# MCU.net
KiCad netlist of a schematic drawn in Altium Designer
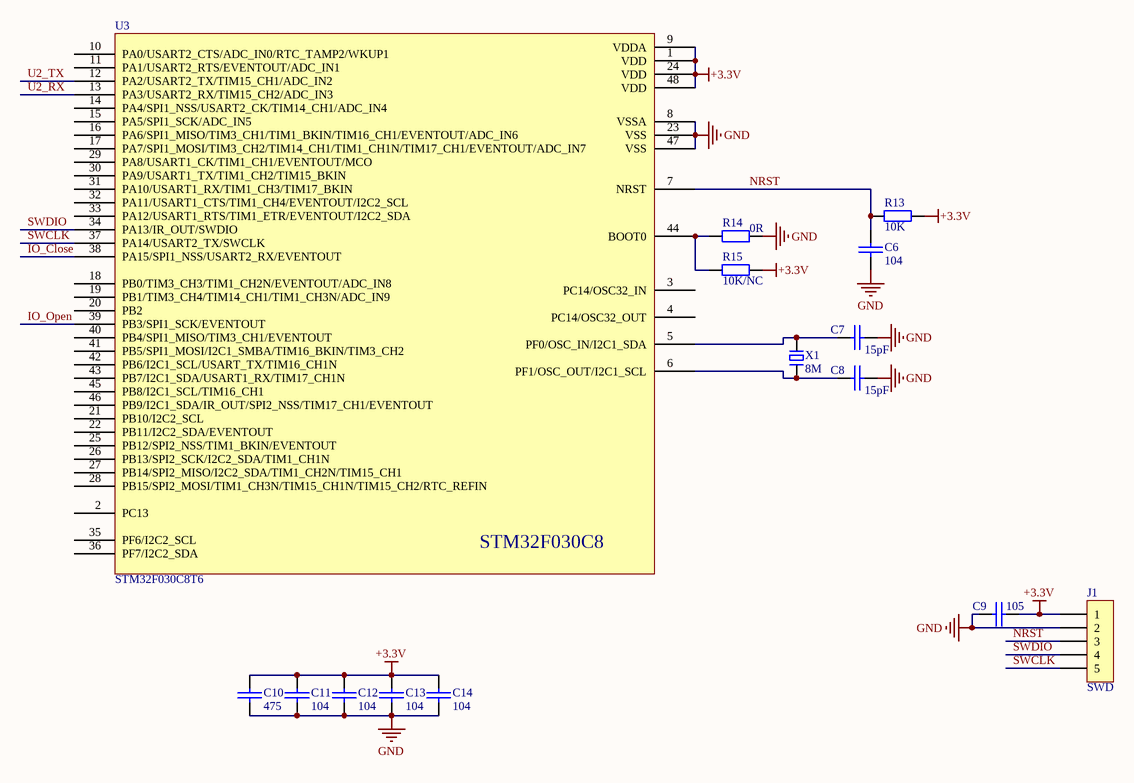
[diagram p0: MCU.SchDoc]

(export (version "E")
  (design (tool "Eeschema 10.0.6"))
  (components
    (comp (ref "C6")
      (value "104")
      (footprint "C0805")
      (description "贴片电容or无极性电容")
      (libsource (lib "LRC") (part "Cap"))
    )
    (comp (ref "C7")
      (value "15pF")
      (footprint "C0805")
      (description "贴片电容or无极性电容")
      (libsource (lib "LRC") (part "Cap"))
    )
    (comp (ref "C8")
      (value "15pF")
      (footprint "C0805")
      (description "贴片电容or无极性电容")
      (libsource (lib "LRC") (part "Cap"))
    )
    (comp (ref "C9")
      (value "105")
      (footprint "C0805")
      (description "贴片电容or无极性电容")
      (libsource (lib "LRC") (part "Cap"))
    )
    (comp (ref "C10")
      (value "475")
      (footprint "C0805")
      (description "贴片电容or无极性电容")
      (libsource (lib "LRC") (part "Cap"))
    )
    (comp (ref "C11")
      (value "104")
      (footprint "C0805")
      (description "贴片电容or无极性电容")
      (libsource (lib "LRC") (part "Cap"))
    )
    (comp (ref "C12")
      (value "104")
      (footprint "C0805")
      (description "贴片电容or无极性电容")
      (libsource (lib "LRC") (part "Cap"))
    )
    (comp (ref "C13")
      (value "104")
      (footprint "C0805")
      (description "贴片电容or无极性电容")
      (libsource (lib "LRC") (part "Cap"))
    )
    (comp (ref "C14")
      (value "104")
      (footprint "C0805")
      (description "贴片电容or无极性电容")
      (libsource (lib "LRC") (part "Cap"))
    )
    (comp (ref "J1")
      (value "SWD")
      (footprint "Fe-HDR1X5/2.54-S")
      (description "2.54MM排母  1x5")
      (libsource (lib "插接件") (part "Female HDR1X5"))
    )
    (comp (ref "R13")
      (value "10K")
      (footprint "R0805")
      (description "电阻")
      (libsource (lib "LRC") (part "Res"))
    )
    (comp (ref "R14")
      (value "0R")
      (footprint "R0805")
      (description "电阻")
      (libsource (lib "LRC") (part "Res"))
    )
    (comp (ref "R15")
      (value "10K/NC")
      (footprint "R0805")
      (description "电阻")
      (libsource (lib "LRC") (part "Res"))
    )
    (comp (ref "U3")
      (value "STM32F030C8T6")
      (footprint "LQFP48 7X7")
      (libsource (lib "IC") (part "STM32f030C8T6"))
    )
    (comp (ref "X1")
      (value "8M")
      (footprint "OSC 5032-2P")
      (description "2脚无源脚晶振")
      (libsource (lib "晶振") (part "XTAL-2P"))
    )
  )
  (nets
    (net (code "1") (name "+3.3V") (class "Default")
      (node (ref "C10") (pin "1") (pinfunction "1_1") (pintype "passive"))
      (node (ref "C11") (pin "1") (pinfunction "1_1") (pintype "passive"))
      (node (ref "C12") (pin "1") (pinfunction "1_1") (pintype "passive"))
      (node (ref "C13") (pin "1") (pinfunction "1_1") (pintype "passive"))
      (node (ref "C14") (pin "1") (pinfunction "1_1") (pintype "passive"))
      (node (ref "C9") (pin "1") (pinfunction "1_1") (pintype "passive"))
      (node (ref "J1") (pin "1") (pinfunction "1_1") (pintype "passive"))
      (node (ref "R13") (pin "2") (pinfunction "2_2") (pintype "passive"))
      (node (ref "R15") (pin "2") (pinfunction "2_2") (pintype "passive"))
      (node (ref "U3") (pin "1") (pinfunction "VDD_1") (pintype "passive"))
      (node (ref "U3") (pin "24") (pinfunction "VDD_24") (pintype "passive"))
      (node (ref "U3") (pin "48") (pinfunction "VDD_48") (pintype "passive"))
      (node (ref "U3") (pin "9") (pinfunction "VDDA_9") (pintype "passive"))
    )
    (net (code "2") (name "/IO_Close") (class "Default")
      (node (ref "U3") (pin "38") (pinfunction "PA15/SPI1_NSS/USART2_RX/EVENTOUT_38") (pintype "passive"))
    )
    (net (code "3") (name "/IO_Open") (class "Default")
      (node (ref "U3") (pin "39") (pinfunction "PB3/SPI1_SCK/EVENTOUT_39") (pintype "passive"))
    )
    (net (code "4") (name "/NRST") (class "Default")
      (node (ref "C6") (pin "1") (pinfunction "1_1") (pintype "passive"))
      (node (ref "J1") (pin "3") (pinfunction "3_3") (pintype "passive"))
      (node (ref "R13") (pin "1") (pinfunction "1_1") (pintype "passive"))
      (node (ref "U3") (pin "7") (pinfunction "NRST_7") (pintype "passive"))
    )
    (net (code "5") (name "/SWCLK") (class "Default")
      (node (ref "J1") (pin "5") (pinfunction "5_5") (pintype "passive"))
      (node (ref "U3") (pin "37") (pinfunction "PA14/USART2_TX/SWCLK_37") (pintype "passive"))
    )
    (net (code "6") (name "/SWDIO") (class "Default")
      (node (ref "J1") (pin "4") (pinfunction "4_4") (pintype "passive"))
      (node (ref "U3") (pin "34") (pinfunction "PA13/IR_OUT/SWDIO_34") (pintype "passive"))
    )
    (net (code "7") (name "/U2_RX") (class "Default")
      (node (ref "U3") (pin "13") (pinfunction "PA3/USART2_RX/TIM15_CH2/ADC_IN3_13") (pintype "passive"))
    )
    (net (code "8") (name "/U2_TX") (class "Default")
      (node (ref "U3") (pin "12") (pinfunction "PA2/USART2_TX/TIM15_CH1/ADC_IN2_12") (pintype "passive"))
    )
    (net (code "9") (name "GND") (class "Default")
      (node (ref "C10") (pin "2") (pinfunction "2_2") (pintype "passive"))
      (node (ref "C11") (pin "2") (pinfunction "2_2") (pintype "passive"))
      (node (ref "C12") (pin "2") (pinfunction "2_2") (pintype "passive"))
      (node (ref "C13") (pin "2") (pinfunction "2_2") (pintype "passive"))
      (node (ref "C14") (pin "2") (pinfunction "2_2") (pintype "passive"))
      (node (ref "C6") (pin "2") (pinfunction "2_2") (pintype "passive"))
      (node (ref "C7") (pin "1") (pinfunction "1_1") (pintype "passive"))
      (node (ref "C8") (pin "1") (pinfunction "1_1") (pintype "passive"))
      (node (ref "C9") (pin "2") (pinfunction "2_2") (pintype "passive"))
      (node (ref "J1") (pin "2") (pinfunction "2_2") (pintype "passive"))
      (node (ref "R14") (pin "2") (pinfunction "2_2") (pintype "passive"))
      (node (ref "U3") (pin "23") (pinfunction "VSS_23") (pintype "passive"))
      (node (ref "U3") (pin "47") (pinfunction "VSS_47") (pintype "passive"))
      (node (ref "U3") (pin "8") (pinfunction "VSSA_8") (pintype "passive"))
    )
    (net (code "10") (name "Net-(U3-BOOT0)") (class "Default")
      (node (ref "R14") (pin "1") (pinfunction "1_1") (pintype "passive"))
      (node (ref "R15") (pin "1") (pinfunction "1_1") (pintype "passive"))
      (node (ref "U3") (pin "44") (pinfunction "BOOT0_44") (pintype "passive"))
    )
    (net (code "11") (name "Net-(U3-PF0{slash}OSC_IN{slash}I2C1_SDA)") (class "Default")
      (node (ref "C7") (pin "2") (pinfunction "2_2") (pintype "passive"))
      (node (ref "U3") (pin "5") (pinfunction "PF0/OSC_IN/I2C1_SDA_5") (pintype "passive"))
      (node (ref "X1") (pin "2") (pinfunction "2_2") (pintype "passive"))
    )
    (net (code "12") (name "Net-(U3-PF1{slash}OSC_OUT{slash}I2C1_SCL)") (class "Default")
      (node (ref "C8") (pin "2") (pinfunction "2_2") (pintype "passive"))
      (node (ref "U3") (pin "6") (pinfunction "PF1/OSC_OUT/I2C1_SCL_6") (pintype "passive"))
      (node (ref "X1") (pin "1") (pinfunction "1_1") (pintype "passive"))
    )
    (net (code "13") (name "unconnected-(U3-PA0{slash}USART2_CTS{slash}ADC_IN0{slash}RTC_TAMP2{slash}WKUP1-Pad10)") (class "Default")
      (node (ref "U3") (pin "10") (pinfunction "PA0/USART2_CTS/ADC_IN0/RTC_TAMP2/WKUP1_10") (pintype "passive"))
    )
    (net (code "14") (name "unconnected-(U3-PA1{slash}USART2_RTS{slash}EVENTOUT{slash}ADC_IN1-Pad11)") (class "Default")
      (node (ref "U3") (pin "11") (pinfunction "PA1/USART2_RTS/EVENTOUT/ADC_IN1_11") (pintype "passive"))
    )
    (net (code "15") (name "unconnected-(U3-PA4{slash}SPI1_NSS{slash}USART2_CK{slash}TIM14_CH1{slash}ADC_IN4-Pad14)") (class "Default")
      (node (ref "U3") (pin "14") (pinfunction "PA4/SPI1_NSS/USART2_CK/TIM14_CH1/ADC_IN4_14") (pintype "passive"))
    )
    (net (code "16") (name "unconnected-(U3-PA5{slash}SPI1_SCK{slash}ADC_IN5-Pad15)") (class "Default")
      (node (ref "U3") (pin "15") (pinfunction "PA5/SPI1_SCK/ADC_IN5_15") (pintype "passive"))
    )
    (net (code "17") (name "unconnected-(U3-PA6{slash}SPI1_MISO{slash}TIM3_CH1{slash}TIM1_BKIN{slash}TIM16_CH1{slash}EVENTOUT{slash}ADC_IN6-Pad16)") (class "Default")
      (node (ref "U3") (pin "16") (pinfunction "PA6/SPI1_MISO/TIM3_CH1/TIM1_BKIN/TIM16_CH1/EVENTOUT/ADC_IN6_16") (pintype "passive"))
    )
    (net (code "18") (name "unconnected-(U3-PA7{slash}SPI1_MOSI{slash}TIM3_CH2{slash}TIM14_CH1{slash}TIM1_CH1N{slash}TIM17_CH1{slash}EVENTOUT{slash}ADC_IN7-Pad17)") (class "Default")
      (node (ref "U3") (pin "17") (pinfunction "PA7/SPI1_MOSI/TIM3_CH2/TIM14_CH1/TIM1_CH1N/TIM17_CH1/EVENTOUT/ADC_IN7_17") (pintype "passive"))
    )
    (net (code "19") (name "unconnected-(U3-PA8{slash}USART1_CK{slash}TIM1_CH1{slash}EVENTOUT{slash}MCO-Pad29)") (class "Default")
      (node (ref "U3") (pin "29") (pinfunction "PA8/USART1_CK/TIM1_CH1/EVENTOUT/MCO_29") (pintype "passive"))
    )
    (net (code "20") (name "unconnected-(U3-PA9{slash}USART1_TX{slash}TIM1_CH2{slash}TIM15_BKIN-Pad30)") (class "Default")
      (node (ref "U3") (pin "30") (pinfunction "PA9/USART1_TX/TIM1_CH2/TIM15_BKIN_30") (pintype "passive"))
    )
    (net (code "21") (name "unconnected-(U3-PA10{slash}USART1_RX{slash}TIM1_CH3{slash}TIM17_BKIN-Pad31)") (class "Default")
      (node (ref "U3") (pin "31") (pinfunction "PA10/USART1_RX/TIM1_CH3/TIM17_BKIN_31") (pintype "passive"))
    )
    (net (code "22") (name "unconnected-(U3-PA11{slash}USART1_CTS{slash}TIM1_CH4{slash}EVENTOUT{slash}I2C2_SCL-Pad32)") (class "Default")
      (node (ref "U3") (pin "32") (pinfunction "PA11/USART1_CTS/TIM1_CH4/EVENTOUT/I2C2_SCL_32") (pintype "passive"))
    )
    (net (code "23") (name "unconnected-(U3-PA12{slash}USART1_RTS{slash}TIM1_ETR{slash}EVENTOUT{slash}I2C2_SDA-Pad33)") (class "Default")
      (node (ref "U3") (pin "33") (pinfunction "PA12/USART1_RTS/TIM1_ETR/EVENTOUT/I2C2_SDA_33") (pintype "passive"))
    )
    (net (code "24") (name "unconnected-(U3-PB0{slash}TIM3_CH3{slash}TIM1_CH2N{slash}EVENTOUT{slash}ADC_IN8-Pad18)") (class "Default")
      (node (ref "U3") (pin "18") (pinfunction "PB0/TIM3_CH3/TIM1_CH2N/EVENTOUT/ADC_IN8_18") (pintype "passive"))
    )
    (net (code "25") (name "unconnected-(U3-PB1{slash}TIM3_CH4{slash}TIM14_CH1{slash}TIM1_CH3N{slash}ADC_IN9-Pad19)") (class "Default")
      (node (ref "U3") (pin "19") (pinfunction "PB1/TIM3_CH4/TIM14_CH1/TIM1_CH3N/ADC_IN9_19") (pintype "passive"))
    )
    (net (code "26") (name "unconnected-(U3-PB2-Pad20)") (class "Default")
      (node (ref "U3") (pin "20") (pinfunction "PB2_20") (pintype "passive"))
    )
    (net (code "27") (name "unconnected-(U3-PB4{slash}SPI1_MISO{slash}TIM3_CH1{slash}EVENTOUT-Pad40)") (class "Default")
      (node (ref "U3") (pin "40") (pinfunction "PB4/SPI1_MISO/TIM3_CH1/EVENTOUT_40") (pintype "passive"))
    )
    (net (code "28") (name "unconnected-(U3-PB5{slash}SPI1_MOSI{slash}I2C1_SMBA{slash}TIM16_BKIN{slash}TIM3_CH2-Pad41)") (class "Default")
      (node (ref "U3") (pin "41") (pinfunction "PB5/SPI1_MOSI/I2C1_SMBA/TIM16_BKIN/TIM3_CH2_41") (pintype "passive"))
    )
    (net (code "29") (name "unconnected-(U3-PB6{slash}I2C1_SCL{slash}USART_TX{slash}TIM16_CH1N-Pad42)") (class "Default")
      (node (ref "U3") (pin "42") (pinfunction "PB6/I2C1_SCL/USART_TX/TIM16_CH1N_42") (pintype "passive"))
    )
    (net (code "30") (name "unconnected-(U3-PB7{slash}I2C1_SDA{slash}USART1_RX{slash}TIM17_CH1N-Pad43)") (class "Default")
      (node (ref "U3") (pin "43") (pinfunction "PB7/I2C1_SDA/USART1_RX/TIM17_CH1N_43") (pintype "passive"))
    )
    (net (code "31") (name "unconnected-(U3-PB8{slash}I2C1_SCL{slash}TIM16_CH1-Pad45)") (class "Default")
      (node (ref "U3") (pin "45") (pinfunction "PB8/I2C1_SCL/TIM16_CH1_45") (pintype "passive"))
    )
    (net (code "32") (name "unconnected-(U3-PB9{slash}I2C1_SDA{slash}IR_OUT{slash}SPI2_NSS{slash}TIM17_CH1{slash}EVENTOUT-Pad46)") (class "Default")
      (node (ref "U3") (pin "46") (pinfunction "PB9/I2C1_SDA/IR_OUT/SPI2_NSS/TIM17_CH1/EVENTOUT_46") (pintype "passive"))
    )
    (net (code "33") (name "unconnected-(U3-PB10{slash}I2C2_SCL-Pad21)") (class "Default")
      (node (ref "U3") (pin "21") (pinfunction "PB10/I2C2_SCL_21") (pintype "passive"))
    )
    (net (code "34") (name "unconnected-(U3-PB11{slash}I2C2_SDA{slash}EVENTOUT-Pad22)") (class "Default")
      (node (ref "U3") (pin "22") (pinfunction "PB11/I2C2_SDA/EVENTOUT_22") (pintype "passive"))
    )
    (net (code "35") (name "unconnected-(U3-PB12{slash}SPI2_NSS{slash}TIM1_BKIN{slash}EVENTOUT-Pad25)") (class "Default")
      (node (ref "U3") (pin "25") (pinfunction "PB12/SPI2_NSS/TIM1_BKIN/EVENTOUT_25") (pintype "passive"))
    )
    (net (code "36") (name "unconnected-(U3-PB13{slash}SPI2_SCK{slash}I2C2_SDA{slash}TIM1_CH1N-Pad26)") (class "Default")
      (node (ref "U3") (pin "26") (pinfunction "PB13/SPI2_SCK/I2C2_SDA/TIM1_CH1N_26") (pintype "passive"))
    )
    (net (code "37") (name "unconnected-(U3-PB14{slash}SPI2_MISO{slash}I2C2_SDA{slash}TIM1_CH2N{slash}TIM15_CH1-Pad27)") (class "Default")
      (node (ref "U3") (pin "27") (pinfunction "PB14/SPI2_MISO/I2C2_SDA/TIM1_CH2N/TIM15_CH1_27") (pintype "passive"))
    )
    (net (code "38") (name "unconnected-(U3-PB15{slash}SPI2_MOSI{slash}TIM1_CH3N{slash}TIM15_CH1N{slash}TIM15_CH2{slash}RTC_REFIN-Pad28)") (class "Default")
      (node (ref "U3") (pin "28") (pinfunction "PB15/SPI2_MOSI/TIM1_CH3N/TIM15_CH1N/TIM15_CH2/RTC_REFIN_28") (pintype "passive"))
    )
    (net (code "39") (name "unconnected-(U3-PC13-Pad2)") (class "Default")
      (node (ref "U3") (pin "2") (pinfunction "PC13_2") (pintype "passive"))
    )
    (net (code "40") (name "unconnected-(U3-PC14{slash}OSC32_IN-Pad3)") (class "Default")
      (node (ref "U3") (pin "3") (pinfunction "PC14/OSC32_IN_3") (pintype "passive"))
    )
    (net (code "41") (name "unconnected-(U3-PC14{slash}OSC32_OUT-Pad4)") (class "Default")
      (node (ref "U3") (pin "4") (pinfunction "PC14/OSC32_OUT_4") (pintype "passive"))
    )
    (net (code "42") (name "unconnected-(U3-PF6{slash}I2C2_SCL-Pad35)") (class "Default")
      (node (ref "U3") (pin "35") (pinfunction "PF6/I2C2_SCL_35") (pintype "passive"))
    )
    (net (code "43") (name "unconnected-(U3-PF7{slash}I2C2_SDA-Pad36)") (class "Default")
      (node (ref "U3") (pin "36") (pinfunction "PF7/I2C2_SDA_36") (pintype "passive"))
    )
  )
)
